# EsquematicoCaneca.net
KiCad netlist of a schematic drawn in Altium Designer
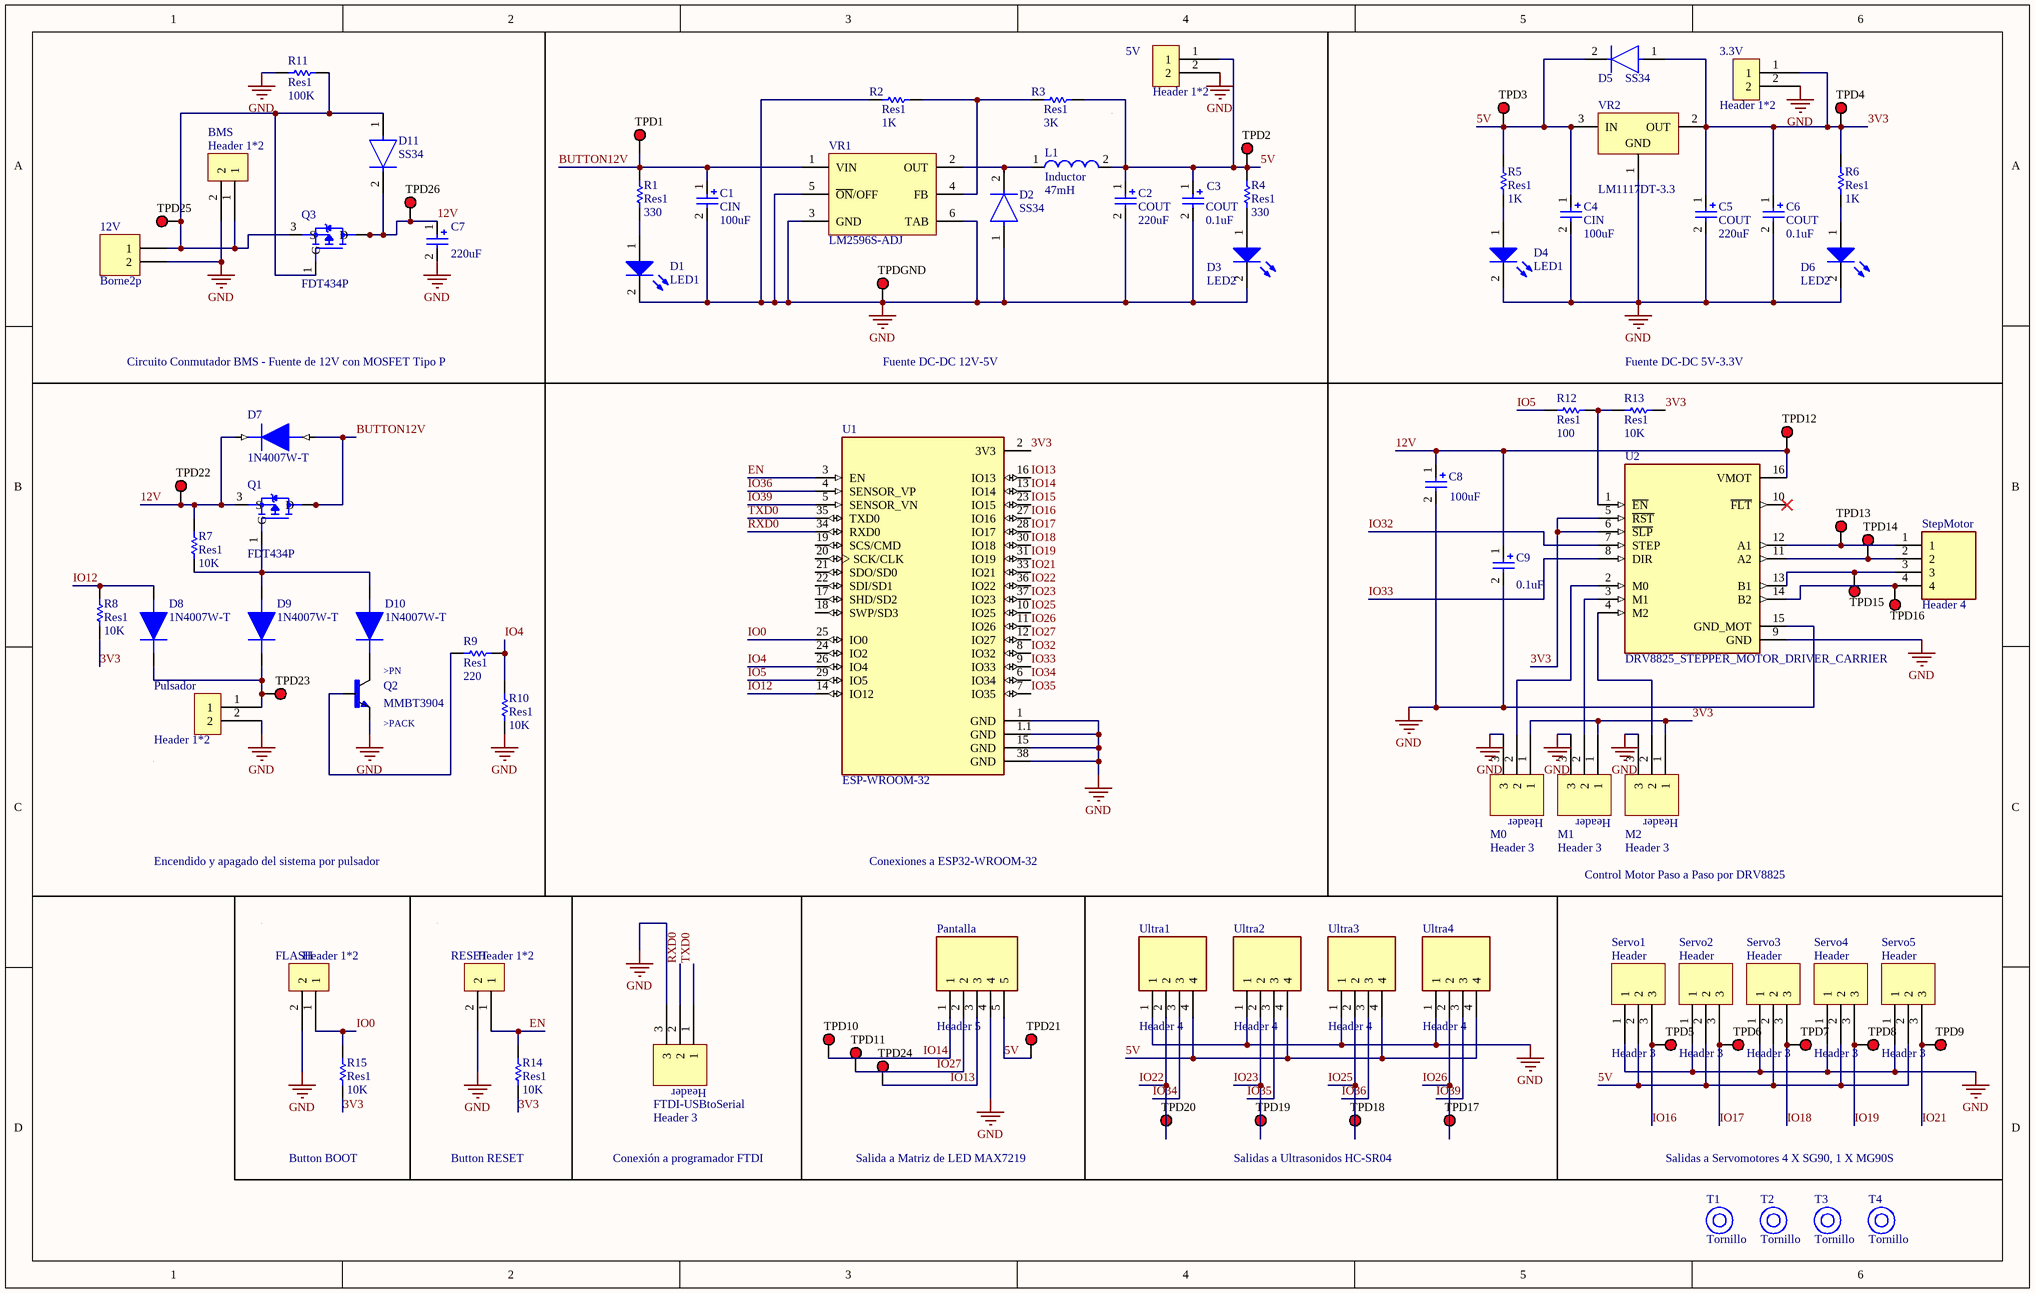
[diagram p0: EsquematicoCaneca.SchDoc]

(export (version "E")
  (design (tool "Eeschema 10.0.6"))
  (components
    (comp (ref "3.3V")
      (value "Header 1*2")
      (footprint "Header 1X2")
      (libsource (lib "ProyectoCaneca") (part "Header 1*2"))
    )
    (comp (ref "5V")
      (value "Header 1*2")
      (footprint "Header 1X2")
      (libsource (lib "ProyectoCaneca") (part "Header 1*2"))
    )
    (comp (ref "12V")
      (value "Borne2p")
      (footprint "Terminal block 1x2 izq")
      (description "Header, 2-Pin")
      (fields (field (name "PUBLISHER") "Altium Limited"))
      (libsource (lib "PCB_Proyecto_Fuente_Voltaje") (part "Header 2"))
    )
    (comp (ref "BMS")
      (value "Header 1*2")
      (footprint "Header 1X2")
      (libsource (lib "") (part "Header 1*2_1"))
    )
    (comp (ref "C1")
      (value "CIN")
      (footprint "CAPACITOR ALUMINUM")
      (description "Polarized Capacitor (Radial)")
      (fields (field (name "ALTIUM_VALUE") "100uF") (field (name "PUBLISHER") "Altium Limited"))
      (libsource (lib "PCB_Proyecto_Fuente_Voltaje") (part "Cap Pol1"))
    )
    (comp (ref "C2")
      (value "COUT")
      (footprint "CAPACITOR ALUMINUM")
      (description "Polarized Capacitor (Radial)")
      (fields (field (name "ALTIUM_VALUE") "220uF") (field (name "PUBLISHER") "Altium Limited"))
      (libsource (lib "PCB_Proyecto_Fuente_Voltaje") (part "Cap Pol1_1"))
    )
    (comp (ref "C3")
      (value "COUT")
      (footprint "CC1206")
      (description "Polarized Capacitor (Radial)")
      (fields (field (name "ALTIUM_VALUE") "0.1uF") (field (name "PUBLISHER") "Altium Limited"))
      (libsource (lib "PCB_Proyecto_Fuente_Voltaje") (part "Cap Pol1_2"))
    )
    (comp (ref "C4")
      (value "CIN")
      (footprint "CAPACITOR ALUMINUM")
      (description "Polarized Capacitor (Radial)")
      (fields (field (name "ALTIUM_VALUE") "100uF") (field (name "PUBLISHER") "Altium Limited"))
      (libsource (lib "PCB_Proyecto_Fuente_Voltaje") (part "Cap Pol1"))
    )
    (comp (ref "C5")
      (value "COUT")
      (footprint "CAPACITOR ALUMINUM")
      (description "Polarized Capacitor (Radial)")
      (fields (field (name "ALTIUM_VALUE") "220uF") (field (name "PUBLISHER") "Altium Limited"))
      (libsource (lib "PCB_Proyecto_Fuente_Voltaje") (part "Cap Pol1_1"))
    )
    (comp (ref "C6")
      (value "COUT")
      (footprint "CC1206")
      (description "Polarized Capacitor (Radial)")
      (fields (field (name "ALTIUM_VALUE") "0.1uF") (field (name "PUBLISHER") "Altium Limited"))
      (libsource (lib "PCB_Proyecto_Fuente_Voltaje") (part "Cap Pol1_2"))
    )
    (comp (ref "C7")
      (value "220uF")
      (footprint "CAPACITOR ALUMINUM")
      (description "Polarized Capacitor (Radial)")
      (fields (field (name "PUBLISHER") "Altium Limited"))
      (libsource (lib "PCB_Proyecto_Fuente_Voltaje") (part "Cap Pol1_1"))
    )
    (comp (ref "C8")
      (value "100uF")
      (footprint "CAPACITOR ALUMINUM")
      (description "Polarized Capacitor (Radial)")
      (fields (field (name "PUBLISHER") "Altium Limited"))
      (libsource (lib "PCB_Proyecto_Fuente_Voltaje") (part "Cap Pol1"))
    )
    (comp (ref "C9")
      (value "0.1uF")
      (footprint "CC1206")
      (description "Polarized Capacitor (Radial)")
      (fields (field (name "PUBLISHER") "Altium Limited"))
      (libsource (lib "PCB_Proyecto_Fuente_Voltaje") (part "Cap Pol1_2"))
    )
    (comp (ref "D1")
      (value "LED1")
      (footprint "LED 0805")
      (description "Typical INFRARED GaAs LED")
      (fields (field (name "PUBLISHER") "Altium Limited"))
      (libsource (lib "PCB_Proyecto_Fuente_Voltaje") (part "LED0_1"))
    )
    (comp (ref "D2")
      (value "SS34")
      (footprint "SS34 DIODE")
      (description "DIODE SCHOTTKY 40V 3A DO214AB")
      (fields (field (name "MANUFACTURER") "Vishay") (field (name "MANUFACTURER PART NUMBER") "SS34-E3/57T"))
      (libsource (lib "biblioteca_esquematica") (part "CMP-02539-000012-1"))
    )
    (comp (ref "D3")
      (value "LED2")
      (footprint "LED 0805")
      (description "Typical INFRARED GaAs LED")
      (fields (field (name "PUBLISHER") "Altium Limited"))
      (libsource (lib "PCB_Proyecto_Fuente_Voltaje") (part "LED0"))
    )
    (comp (ref "D4")
      (value "LED1")
      (footprint "LED 0805")
      (description "Typical INFRARED GaAs LED")
      (fields (field (name "PUBLISHER") "Altium Limited"))
      (libsource (lib "PCB_Proyecto_Fuente_Voltaje") (part "LED0"))
    )
    (comp (ref "D5")
      (value "SS34")
      (footprint "SS34 DIODE")
      (description "DIODE SCHOTTKY 40V 3A DO214AB")
      (fields (field (name "MANUFACTURER") "Vishay") (field (name "MANUFACTURER PART NUMBER") "SS34-E3/57T"))
      (libsource (lib "biblioteca_esquematica") (part "CMP-02539-000012-1"))
    )
    (comp (ref "D6")
      (value "LED2")
      (footprint "LED 0805")
      (description "Typical INFRARED GaAs LED")
      (fields (field (name "PUBLISHER") "Altium Limited"))
      (libsource (lib "PCB_Proyecto_Fuente_Voltaje") (part "LED0"))
    )
    (comp (ref "D7")
      (value "1N4007W-T")
      (footprint "SODFL3818X130N")
      (description "STANDARD SOD123FL T/R 3000")
      (fields (field (name "MF") "EIC") (field (name "MP") "1N4007W"))
      (libsource (lib "ProyectoCaneca") (part "1N4007W-T"))
    )
    (comp (ref "D8")
      (value "1N4007W-T")
      (footprint "SODFL3818X130N")
      (description "STANDARD SOD123FL T/R 3000")
      (fields (field (name "MF") "EIC") (field (name "MP") "1N4007W"))
      (libsource (lib "ProyectoCaneca") (part "1N4007W-T"))
    )
    (comp (ref "D9")
      (value "1N4007W-T")
      (footprint "SODFL3818X130N")
      (description "STANDARD SOD123FL T/R 3000")
      (fields (field (name "MF") "EIC") (field (name "MP") "1N4007W"))
      (libsource (lib "ProyectoCaneca") (part "1N4007W-T"))
    )
    (comp (ref "D10")
      (value "1N4007W-T")
      (footprint "SODFL3818X130N")
      (description "STANDARD SOD123FL T/R 3000")
      (fields (field (name "MF") "EIC") (field (name "MP") "1N4007W"))
      (libsource (lib "ProyectoCaneca") (part "1N4007W-T"))
    )
    (comp (ref "D11")
      (value "SS34")
      (footprint "SS34 DIODE")
      (description "DIODE SCHOTTKY 40V 3A DO214AB")
      (fields (field (name "MANUFACTURER") "Vishay") (field (name "MANUFACTURER PART NUMBER") "SS34-E3/57T"))
      (libsource (lib "biblioteca_esquematica") (part "CMP-02539-000012-1"))
    )
    (comp (ref "FLASH")
      (value "Header 1*2")
      (footprint "Header 1X2")
      (libsource (lib "") (part "Header 1*2_1"))
    )
    (comp (ref "FTDI-USBtoSerial")
      (value "Header 3")
      (footprint "header 1x3")
      (libsource (lib "") (part "Header 3_1"))
    )
    (comp (ref "L1")
      (value "Inductor")
      (footprint "INDUCTOR")
      (fields (field (name "ALTIUM_VALUE") "47mH") (field (name "PUBLISHER") "Altium Limited"))
      (libsource (lib "PCB_Proyecto_Fuente_Voltaje") (part "Inductor"))
    )
    (comp (ref "M0") (value "Header 3") (footprint "header 1x3") (libsource (lib "") (part "Header 3_1")))
    (comp (ref "M1") (value "Header 3") (footprint "header 1x3") (libsource (lib "") (part "Header 3_1")))
    (comp (ref "M2") (value "Header 3") (footprint "header 1x3") (libsource (lib "") (part "Header 3_1")))
    (comp (ref "Pantalla")
      (value "Header 5")
      (footprint "HEADER X 5")
      (description "Board-To-Board Connector, Through Hole, Header, 5, 2.54 mm, Gold Plated Contacts")
      (fields (field (name "MF") "TE Connectivity") (field (name "MP") "826646-5"))
      (libsource (lib "ProyectoCaneca") (part "Header 5"))
    )
    (comp (ref "Pulsador")
      (value "Header 1*2")
      (footprint "Header 1X2")
      (libsource (lib "ProyectoCaneca") (part "Header 1*2"))
    )
    (comp (ref "Q1")
      (value "FDT434P")
      (footprint "SOT230P700X180-4N")
      (description "P-Channel 20 V 6A (Ta) 3W (Ta) Surface Mount SOT-223-4")
      (fields (field (name "MF") "ON"))
      (libsource (lib "ProyectoCaneca") (part "FDT434P"))
    )
    (comp (ref "Q2")
      (value "MMBT3904")
      (footprint "MMBT3904")
      (libsource (lib "ProyectoCaneca") (part "MMBT3904"))
    )
    (comp (ref "Q3")
      (value "FDT434P")
      (footprint "SOT230P700X180-4N")
      (description "P-Channel 20 V 6A (Ta) 3W (Ta) Surface Mount SOT-223-4")
      (fields (field (name "MF") "ON"))
      (libsource (lib "ProyectoCaneca") (part "FDT434P"))
    )
    (comp (ref "R1")
      (value "Res1")
      (footprint "RESISTOR 1206")
      (description "Resistor")
      (fields (field (name "ALTIUM_VALUE") "330") (field (name "PUBLISHER") "Altium Limited"))
      (libsource (lib "PCB_Proyecto_Fuente_Voltaje") (part "Res1_2"))
    )
    (comp (ref "R2")
      (value "Res1")
      (footprint "RESISTOR 1206")
      (description "Resistor")
      (fields (field (name "ALTIUM_VALUE") "1K") (field (name "PUBLISHER") "Altium Limited"))
      (libsource (lib "PCB_Proyecto_Fuente_Voltaje") (part "Res1"))
    )
    (comp (ref "R3")
      (value "Res1")
      (footprint "RESISTOR 1206")
      (description "Resistor")
      (fields (field (name "ALTIUM_VALUE") "3K") (field (name "PUBLISHER") "Altium Limited"))
      (libsource (lib "PCB_Proyecto_Fuente_Voltaje") (part "Res1_1"))
    )
    (comp (ref "R4")
      (value "Res1")
      (footprint "RESISTOR 1206")
      (description "Resistor")
      (fields (field (name "ALTIUM_VALUE") "330") (field (name "PUBLISHER") "Altium Limited"))
      (libsource (lib "PCB_Proyecto_Fuente_Voltaje") (part "Res1_2"))
    )
    (comp (ref "R5")
      (value "Res1")
      (footprint "RESISTOR 1206")
      (description "Resistor")
      (fields (field (name "ALTIUM_VALUE") "1K") (field (name "PUBLISHER") "Altium Limited"))
      (libsource (lib "PCB_Proyecto_Fuente_Voltaje") (part "Res1"))
    )
    (comp (ref "R6")
      (value "Res1")
      (footprint "RESISTOR 1206")
      (description "Resistor")
      (fields (field (name "ALTIUM_VALUE") "1K") (field (name "PUBLISHER") "Altium Limited"))
      (libsource (lib "PCB_Proyecto_Fuente_Voltaje") (part "Res1"))
    )
    (comp (ref "R7")
      (value "Res1")
      (footprint "RESISTOR 1206")
      (description "Resistor")
      (fields (field (name "ALTIUM_VALUE") "10K") (field (name "PUBLISHER") "Altium Limited"))
      (libsource (lib "PCB_Proyecto_Fuente_Voltaje") (part "Res1"))
    )
    (comp (ref "R8")
      (value "Res1")
      (footprint "RESISTOR 1206")
      (description "Resistor")
      (fields (field (name "ALTIUM_VALUE") "10K") (field (name "PUBLISHER") "Altium Limited"))
      (libsource (lib "PCB_Proyecto_Fuente_Voltaje") (part "Res1"))
    )
    (comp (ref "R9")
      (value "Res1")
      (footprint "RESISTOR 1206")
      (description "Resistor")
      (fields (field (name "ALTIUM_VALUE") "220") (field (name "PUBLISHER") "Altium Limited"))
      (libsource (lib "PCB_Proyecto_Fuente_Voltaje") (part "Res1"))
    )
    (comp (ref "R10")
      (value "Res1")
      (footprint "RESISTOR 1206")
      (description "Resistor")
      (fields (field (name "ALTIUM_VALUE") "10K") (field (name "PUBLISHER") "Altium Limited"))
      (libsource (lib "PCB_Proyecto_Fuente_Voltaje") (part "Res1"))
    )
    (comp (ref "R11")
      (value "Res1")
      (footprint "RESISTOR 1206")
      (description "Resistor")
      (fields (field (name "ALTIUM_VALUE") "100K") (field (name "PUBLISHER") "Altium Limited"))
      (libsource (lib "PCB_Proyecto_Fuente_Voltaje") (part "Res1"))
    )
    (comp (ref "R12")
      (value "Res1")
      (footprint "RESISTOR 1206")
      (description "Resistor")
      (fields (field (name "ALTIUM_VALUE") "100") (field (name "PUBLISHER") "Altium Limited"))
      (libsource (lib "PCB_Proyecto_Fuente_Voltaje") (part "Res1"))
    )
    (comp (ref "R13")
      (value "Res1")
      (footprint "RESISTOR 1206")
      (description "Resistor")
      (fields (field (name "ALTIUM_VALUE") "10K") (field (name "PUBLISHER") "Altium Limited"))
      (libsource (lib "PCB_Proyecto_Fuente_Voltaje") (part "Res1"))
    )
    (comp (ref "R14")
      (value "Res1")
      (footprint "RESISTOR 1206")
      (description "Resistor")
      (fields (field (name "ALTIUM_VALUE") "10K") (field (name "PUBLISHER") "Altium Limited"))
      (libsource (lib "PCB_Proyecto_Fuente_Voltaje") (part "Res1"))
    )
    (comp (ref "R15")
      (value "Res1")
      (footprint "RESISTOR 1206")
      (description "Resistor")
      (fields (field (name "ALTIUM_VALUE") "10K") (field (name "PUBLISHER") "Altium Limited"))
      (libsource (lib "PCB_Proyecto_Fuente_Voltaje") (part "Res1"))
    )
    (comp (ref "RESET")
      (value "Header 1*2")
      (footprint "Header 1X2")
      (libsource (lib "") (part "Header 1*2_1"))
    )
    (comp (ref "Servo1")
      (value "Header 3")
      (footprint "header 1x3")
      (libsource (lib "ProyectoCaneca") (part "Header 3"))
    )
    (comp (ref "Servo2")
      (value "Header 3")
      (footprint "header 1x3")
      (libsource (lib "ProyectoCaneca") (part "Header 3"))
    )
    (comp (ref "Servo3")
      (value "Header 3")
      (footprint "header 1x3")
      (libsource (lib "ProyectoCaneca") (part "Header 3"))
    )
    (comp (ref "Servo4")
      (value "Header 3")
      (footprint "header 1x3")
      (libsource (lib "ProyectoCaneca") (part "Header 3"))
    )
    (comp (ref "Servo5")
      (value "Header 3")
      (footprint "header 1x3")
      (libsource (lib "ProyectoCaneca") (part "Header 3"))
    )
    (comp (ref "StepMotor")
      (value "Header 4")
      (footprint "HEADER 1X4")
      (fields (field (name "MP") "640453-4") (field (name "MF") "{'manufacturer': 'TE Connectivity'}"))
      (libsource (lib "") (part "Header 4_1"))
    )
    (comp (ref "T1")
      (value "Tornillo")
      (footprint "TORNILLO")
      (libsource (lib "PCB_Proyecto_Fuente_Voltaje") (part "Tornillo"))
    )
    (comp (ref "T2")
      (value "Tornillo")
      (footprint "TORNILLO")
      (libsource (lib "PCB_Proyecto_Fuente_Voltaje") (part "Tornillo"))
    )
    (comp (ref "T3")
      (value "Tornillo")
      (footprint "TORNILLO")
      (libsource (lib "PCB_Proyecto_Fuente_Voltaje") (part "Tornillo"))
    )
    (comp (ref "T4")
      (value "Tornillo")
      (footprint "TORNILLO")
      (libsource (lib "PCB_Proyecto_Fuente_Voltaje") (part "Tornillo"))
    )
    (comp (ref "TPD1")
      (value "~")
      (footprint "TESTPOINT SMT")
      (description "Test Point, Red, Through Hole, RoHS, Bulk")
      (fields (field (name "MANUFACTURER") "Keystone"))
      (libsource (lib "Schlib2") (part "TestPointRed"))
    )
    (comp (ref "TPD2")
      (value "~")
      (footprint "TESTPOINT SMT")
      (description "Test Point, Red, Through Hole, RoHS, Bulk")
      (fields (field (name "MANUFACTURER") "Keystone"))
      (libsource (lib "Schlib2") (part "TestPointRed"))
    )
    (comp (ref "TPD3")
      (value "~")
      (footprint "TESTPOINT SMT")
      (description "Test Point, Red, Through Hole, RoHS, Bulk")
      (fields (field (name "MANUFACTURER") "Keystone"))
      (libsource (lib "Schlib2") (part "TestPointRed"))
    )
    (comp (ref "TPD4")
      (value "~")
      (footprint "TESTPOINT SMT")
      (description "Test Point, Red, Through Hole, RoHS, Bulk")
      (fields (field (name "MANUFACTURER") "Keystone"))
      (libsource (lib "Schlib2") (part "TestPointRed"))
    )
    (comp (ref "TPD5")
      (value "~")
      (footprint "TESTPOINT SMT")
      (description "Test Point, Red, Through Hole, RoHS, Bulk")
      (fields (field (name "MANUFACTURER") "Keystone"))
      (libsource (lib "Schlib2") (part "TestPointRed"))
    )
    (comp (ref "TPD6")
      (value "~")
      (footprint "TESTPOINT SMT")
      (description "Test Point, Red, Through Hole, RoHS, Bulk")
      (fields (field (name "MANUFACTURER") "Keystone"))
      (libsource (lib "Schlib2") (part "TestPointRed"))
    )
    (comp (ref "TPD7")
      (value "~")
      (footprint "TESTPOINT SMT")
      (description "Test Point, Red, Through Hole, RoHS, Bulk")
      (fields (field (name "MANUFACTURER") "Keystone"))
      (libsource (lib "Schlib2") (part "TestPointRed"))
    )
    (comp (ref "TPD8")
      (value "~")
      (footprint "TESTPOINT SMT")
      (description "Test Point, Red, Through Hole, RoHS, Bulk")
      (fields (field (name "MANUFACTURER") "Keystone"))
      (libsource (lib "Schlib2") (part "TestPointRed"))
    )
    (comp (ref "TPD9")
      (value "~")
      (footprint "TESTPOINT SMT")
      (description "Test Point, Red, Through Hole, RoHS, Bulk")
      (fields (field (name "MANUFACTURER") "Keystone"))
      (libsource (lib "Schlib2") (part "TestPointRed"))
    )
    (comp (ref "TPD10")
      (value "~")
      (footprint "TESTPOINT SMT")
      (description "Test Point, Red, Through Hole, RoHS, Bulk")
      (fields (field (name "MANUFACTURER") "Keystone"))
      (libsource (lib "Schlib2") (part "TestPointRed"))
    )
    (comp (ref "TPD11")
      (value "~")
      (footprint "TESTPOINT SMT")
      (description "Test Point, Red, Through Hole, RoHS, Bulk")
      (fields (field (name "MANUFACTURER") "Keystone"))
      (libsource (lib "Schlib2") (part "TestPointRed"))
    )
    (comp (ref "TPD12")
      (value "~")
      (footprint "TESTPOINT SMT")
      (description "Test Point, Red, Through Hole, RoHS, Bulk")
      (fields (field (name "MANUFACTURER") "Keystone"))
      (libsource (lib "Schlib2") (part "TestPointRed"))
    )
    (comp (ref "TPD13")
      (value "~")
      (footprint "TESTPOINT SMT")
      (description "Test Point, Red, Through Hole, RoHS, Bulk")
      (fields (field (name "MANUFACTURER") "Keystone"))
      (libsource (lib "Schlib2") (part "TestPointRed"))
    )
    (comp (ref "TPD14")
      (value "~")
      (footprint "TESTPOINT SMT")
      (description "Test Point, Red, Through Hole, RoHS, Bulk")
      (fields (field (name "MANUFACTURER") "Keystone"))
      (libsource (lib "Schlib2") (part "TestPointRed"))
    )
    (comp (ref "TPD15")
      (value "~")
      (footprint "TESTPOINT SMT")
      (description "Test Point, Red, Through Hole, RoHS, Bulk")
      (fields (field (name "MANUFACTURER") "Keystone"))
      (libsource (lib "Schlib2") (part "TestPointRed"))
    )
    (comp (ref "TPD16")
      (value "~")
      (footprint "TESTPOINT SMT")
      (description "Test Point, Red, Through Hole, RoHS, Bulk")
      (fields (field (name "MANUFACTURER") "Keystone"))
      (libsource (lib "Schlib2") (part "TestPointRed"))
    )
    (comp (ref "TPD17")
      (value "~")
      (footprint "TESTPOINT SMT")
      (description "Test Point, Red, Through Hole, RoHS, Bulk")
      (fields (field (name "MANUFACTURER") "Keystone"))
      (libsource (lib "Schlib2") (part "TestPointRed"))
    )
    (comp (ref "TPD18")
      (value "~")
      (footprint "TESTPOINT SMT")
      (description "Test Point, Red, Through Hole, RoHS, Bulk")
      (fields (field (name "MANUFACTURER") "Keystone"))
      (libsource (lib "Schlib2") (part "TestPointRed"))
    )
    (comp (ref "TPD19")
      (value "~")
      (footprint "TESTPOINT SMT")
      (description "Test Point, Red, Through Hole, RoHS, Bulk")
      (fields (field (name "MANUFACTURER") "Keystone"))
      (libsource (lib "Schlib2") (part "TestPointRed"))
    )
    (comp (ref "TPD20")
      (value "~")
      (footprint "TESTPOINT SMT")
      (description "Test Point, Red, Through Hole, RoHS, Bulk")
      (fields (field (name "MANUFACTURER") "Keystone"))
      (libsource (lib "Schlib2") (part "TestPointRed"))
    )
    (comp (ref "TPD21")
      (value "~")
      (footprint "TESTPOINT SMT")
      (description "Test Point, Red, Through Hole, RoHS, Bulk")
      (fields (field (name "MANUFACTURER") "Keystone"))
      (libsource (lib "Schlib2") (part "TestPointRed"))
    )
    (comp (ref "TPD22")
      (value "~")
      (footprint "TESTPOINT SMT")
      (description "Test Point, Red, Through Hole, RoHS, Bulk")
      (fields (field (name "MANUFACTURER") "Keystone"))
      (libsource (lib "Schlib2") (part "TestPointRed"))
    )
    (comp (ref "TPD23")
      (value "~")
      (footprint "TESTPOINT SMT")
      (description "Test Point, Red, Through Hole, RoHS, Bulk")
      (fields (field (name "MANUFACTURER") "Keystone"))
      (libsource (lib "Schlib2") (part "TestPointRed"))
    )
    (comp (ref "TPD24")
      (value "~")
      (footprint "TESTPOINT SMT")
      (description "Test Point, Red, Through Hole, RoHS, Bulk")
      (fields (field (name "MANUFACTURER") "Keystone"))
      (libsource (lib "Schlib2") (part "TestPointRed"))
    )
    (comp (ref "TPD25")
      (value "~")
      (footprint "TESTPOINT SMT")
      (description "Test Point, Red, Through Hole, RoHS, Bulk")
      (fields (field (name "MANUFACTURER") "Keystone"))
      (libsource (lib "Schlib2") (part "TestPointRed"))
    )
    (comp (ref "TPD26")
      (value "~")
      (footprint "TESTPOINT SMT")
      (description "Test Point, Red, Through Hole, RoHS, Bulk")
      (fields (field (name "MANUFACTURER") "Keystone"))
      (libsource (lib "Schlib2") (part "TestPointRed"))
    )
    (comp (ref "TPDGND")
      (value "~")
      (footprint "TESTPOINT SMT")
      (description "Test Point, Red, Through Hole, RoHS, Bulk")
      (fields (field (name "MANUFACTURER") "Keystone"))
      (libsource (lib "Schlib2") (part "TestPointRed"))
    )
    (comp (ref "U1")
      (value "ESP-WROOM-32")
      (footprint "MODULE_ESP-WROOM-32")
      (fields (field (name "MF") "Espressif Systems"))
      (libsource (lib "ProyectoCaneca") (part "ESP-WROOM-32"))
    )
    (comp (ref "U2")
      (value "DRV8825_STEPPER_MOTOR_DRIVER_CARRIER")
      (footprint "IC_DRV8825_STEPPER_MOTOR_DRIVER_CARRIER")
      (description "Stepper motor controler; IC: DRV8825; 1.5A; Uin mot: 8.2Ã·45V")
      (libsource (lib "ProyectoCaneca") (part "DRV8825_STEPPER_MOTOR_DRIVER_CARRIER"))
    )
    (comp (ref "Ultra1")
      (value "Header 4")
      (footprint "HEADER 1X4")
      (fields (field (name "MP") "640453-4") (field (name "MF") "{'manufacturer': 'TE Connectivity'}"))
      (libsource (lib "ProyectoCaneca") (part "Header 4"))
    )
    (comp (ref "Ultra2")
      (value "Header 4")
      (footprint "HEADER 1X4")
      (fields (field (name "MP") "640453-4") (field (name "MF") "{'manufacturer': 'TE Connectivity'}"))
      (libsource (lib "ProyectoCaneca") (part "Header 4"))
    )
    (comp (ref "Ultra3")
      (value "Header 4")
      (footprint "HEADER 1X4")
      (fields (field (name "MP") "640453-4") (field (name "MF") "{'manufacturer': 'TE Connectivity'}"))
      (libsource (lib "ProyectoCaneca") (part "Header 4"))
    )
    (comp (ref "Ultra4")
      (value "Header 4")
      (footprint "HEADER 1X4")
      (fields (field (name "MP") "640453-4") (field (name "MF") "{'manufacturer': 'TE Connectivity'}"))
      (libsource (lib "ProyectoCaneca") (part "Header 4"))
    )
    (comp (ref "VR1")
      (value "LM2596S-ADJ")
      (footprint "lm2596S")
      (description "SIMPLE SWITCHER® Power Converter 150 KHz 3A Step-Down Voltage Regulator, 5-pin TO-263")
      (fields
        (field (name "MANUFACTURER") "National Semiconductor")
        (field (name "MANUFACTURER_1") "TI National Semiconductor")
      )
      (libsource (lib "PCB_Proyecto_Fuente_Voltaje") (part "LM2596S-ADJ"))
    )
    (comp (ref "VR2")
      (value "LM1117DT-3.3")
      (footprint "LM1117DT-3.3")
      (description "800mA Low-Dropout Linear Regulator, 3-pin TO-252")
      (fields
        (field (name "MANUFACTURER") "National Semiconductor")
        (field (name "MANUFACTURER_1") "TI National Semiconductor")
      )
      (libsource (lib "PCB_Proyecto_Fuente_Voltaje") (part "LM1117DT-3.3"))
    )
  )
  (nets
    (net (code "1") (name "/3V3") (class "Default")
      (node (ref "3.3V") (pin "1") (pinfunction "1_1") (pintype "passive"))
      (node (ref "C5") (pin "1") (pinfunction "1_1") (pintype "passive"))
      (node (ref "C6") (pin "1") (pinfunction "1_1") (pintype "passive"))
      (node (ref "D5") (pin "1") (pinfunction "A_1") (pintype "passive"))
      (node (ref "M0") (pin "1") (pinfunction "1_1") (pintype "passive"))
      (node (ref "M1") (pin "1") (pinfunction "1_1") (pintype "passive"))
      (node (ref "M2") (pin "1") (pinfunction "1_1") (pintype "passive"))
      (node (ref "R13") (pin "1") (pinfunction "1_1") (pintype "passive"))
      (node (ref "R14") (pin "1") (pinfunction "1_1") (pintype "passive"))
      (node (ref "R15") (pin "1") (pinfunction "1_1") (pintype "passive"))
      (node (ref "R6") (pin "2") (pinfunction "2_2") (pintype "passive"))
      (node (ref "R8") (pin "1") (pinfunction "1_1") (pintype "passive"))
      (node (ref "TPD4") (pin "1") (pinfunction "1_1") (pintype "passive"))
      (node (ref "U1") (pin "2") (pinfunction "3V3_2") (pintype "power_in"))
      (node (ref "U2") (pin "5") (pinfunction "~{RST}_5") (pintype "input"))
      (node (ref "U2") (pin "6") (pinfunction "~{SLP}_6") (pintype "input"))
      (node (ref "VR2") (pin "2") (pinfunction "OUT_2") (pintype "power_in"))
    )
    (net (code "2") (name "/5V") (class "Default")
      (node (ref "5V") (pin "1") (pinfunction "1_1") (pintype "passive"))
      (node (ref "C2") (pin "1") (pinfunction "1_1") (pintype "passive"))
      (node (ref "C3") (pin "1") (pinfunction "1_1") (pintype "passive"))
      (node (ref "C4") (pin "1") (pinfunction "1_1") (pintype "passive"))
      (node (ref "D5") (pin "2") (pinfunction "C_2") (pintype "passive"))
      (node (ref "L1") (pin "2") (pinfunction "2_2") (pintype "passive"))
      (node (ref "Pantalla") (pin "5") (pinfunction "5_5") (pintype "passive"))
      (node (ref "R3") (pin "2") (pinfunction "2_2") (pintype "passive"))
      (node (ref "R4") (pin "2") (pinfunction "2_2") (pintype "passive"))
      (node (ref "R5") (pin "2") (pinfunction "2_2") (pintype "passive"))
      (node (ref "Servo1") (pin "2") (pinfunction "2_2") (pintype "passive"))
      (node (ref "Servo2") (pin "2") (pinfunction "2_2") (pintype "passive"))
      (node (ref "Servo3") (pin "2") (pinfunction "2_2") (pintype "passive"))
      (node (ref "Servo4") (pin "2") (pinfunction "2_2") (pintype "passive"))
      (node (ref "Servo5") (pin "2") (pinfunction "2_2") (pintype "passive"))
      (node (ref "TPD2") (pin "1") (pinfunction "1_1") (pintype "passive"))
      (node (ref "TPD21") (pin "1") (pinfunction "1_1") (pintype "passive"))
      (node (ref "TPD3") (pin "1") (pinfunction "1_1") (pintype "passive"))
      (node (ref "Ultra1") (pin "4") (pinfunction "4_4") (pintype "passive"))
      (node (ref "Ultra2") (pin "4") (pinfunction "4_4") (pintype "passive"))
      (node (ref "Ultra3") (pin "4") (pinfunction "4_4") (pintype "passive"))
      (node (ref "Ultra4") (pin "4") (pinfunction "4_4") (pintype "passive"))
      (node (ref "VR2") (pin "3") (pinfunction "IN_3") (pintype "power_in"))
    )
    (net (code "3") (name "/12V") (class "Default")
      (node (ref "C7") (pin "1") (pinfunction "1_1") (pintype "passive"))
      (node (ref "C8") (pin "1") (pinfunction "1_1") (pintype "passive"))
      (node (ref "C9") (pin "1") (pinfunction "1_1") (pintype "passive"))
      (node (ref "D11") (pin "2") (pinfunction "C_2") (pintype "passive"))
      (node (ref "D7") (pin "1") (pinfunction "K_1") (pintype "bidirectional"))
      (node (ref "Q1") (pin "3") (pinfunction "S_3") (pintype "passive"))
      (node (ref "Q3") (pin "2") (pinfunction "D_2") (pintype "passive"))
      (node (ref "Q3") (pin "4") (pinfunction "D_4") (pintype "passive"))
      (node (ref "R7") (pin "2") (pinfunction "2_2") (pintype "passive"))
      (node (ref "TPD12") (pin "1") (pinfunction "1_1") (pintype "passive"))
      (node (ref "TPD22") (pin "1") (pinfunction "1_1") (pintype "passive"))
      (node (ref "TPD26") (pin "1") (pinfunction "1_1") (pintype "passive"))
      (node (ref "U2") (pin "16") (pinfunction "VMOT_16") (pintype "power_in"))
    )
    (net (code "4") (name "/BUTTON12V") (class "Default")
      (node (ref "C1") (pin "1") (pinfunction "1_1") (pintype "passive"))
      (node (ref "D7") (pin "2") (pinfunction "A_2") (pintype "bidirectional"))
      (node (ref "Q1") (pin "2") (pinfunction "D_2") (pintype "passive"))
      (node (ref "Q1") (pin "4") (pinfunction "D_4") (pintype "passive"))
      (node (ref "R1") (pin "2") (pinfunction "2_2") (pintype "passive"))
      (node (ref "TPD1") (pin "1") (pinfunction "1_1") (pintype "passive"))
      (node (ref "VR1") (pin "1") (pinfunction "VIN_1") (pintype "power_in"))
    )
    (net (code "5") (name "/EN") (class "Default")
      (node (ref "R14") (pin "2") (pinfunction "2_2") (pintype "passive"))
      (node (ref "RESET") (pin "1") (pinfunction "1_1") (pintype "passive"))
      (node (ref "U1") (pin "3") (pinfunction "EN_3") (pintype "input"))
    )
    (net (code "6") (name "/IO0") (class "Default")
      (node (ref "FLASH") (pin "1") (pinfunction "1_1") (pintype "passive"))
      (node (ref "R15") (pin "2") (pinfunction "2_2") (pintype "passive"))
      (node (ref "U1") (pin "25") (pinfunction "IO0_25") (pintype "bidirectional"))
    )
    (net (code "7") (name "/IO4") (class "Default")
      (node (ref "R10") (pin "2") (pinfunction "2_2") (pintype "passive"))
      (node (ref "R9") (pin "2") (pinfunction "2_2") (pintype "passive"))
      (node (ref "U1") (pin "26") (pinfunction "IO4_26") (pintype "bidirectional"))
    )
    (net (code "8") (name "/IO5") (class "Default")
      (node (ref "R12") (pin "1") (pinfunction "1_1") (pintype "passive"))
      (node (ref "U1") (pin "29") (pinfunction "IO5_29") (pintype "bidirectional"))
    )
    (net (code "9") (name "/IO12") (class "Default")
      (node (ref "D8") (pin "2") (pinfunction "A_2") (pintype "bidirectional"))
      (node (ref "R8") (pin "2") (pinfunction "2_2") (pintype "passive"))
      (node (ref "U1") (pin "14") (pinfunction "IO12_14") (pintype "bidirectional"))
    )
    (net (code "10") (name "/IO13") (class "Default")
      (node (ref "Pantalla") (pin "3") (pinfunction "3_3") (pintype "passive"))
      (node (ref "TPD24") (pin "1") (pinfunction "1_1") (pintype "passive"))
      (node (ref "U1") (pin "16") (pinfunction "IO13_16") (pintype "bidirectional"))
    )
    (net (code "11") (name "/IO14") (class "Default")
      (node (ref "Pantalla") (pin "1") (pinfunction "1_1") (pintype "passive"))
      (node (ref "TPD10") (pin "1") (pinfunction "1_1") (pintype "passive"))
      (node (ref "U1") (pin "13") (pinfunction "IO14_13") (pintype "bidirectional"))
    )
    (net (code "12") (name "/IO15") (class "Default")
      (node (ref "U1") (pin "23") (pinfunction "IO15_23") (pintype "bidirectional"))
    )
    (net (code "13") (name "/IO16") (class "Default")
      (node (ref "Servo1") (pin "3") (pinfunction "3_3") (pintype "passive"))
      (node (ref "TPD5") (pin "1") (pinfunction "1_1") (pintype "passive"))
      (node (ref "U1") (pin "27") (pinfunction "IO16_27") (pintype "bidirectional"))
    )
    (net (code "14") (name "/IO17") (class "Default")
      (node (ref "Servo2") (pin "3") (pinfunction "3_3") (pintype "passive"))
      (node (ref "TPD6") (pin "1") (pinfunction "1_1") (pintype "passive"))
      (node (ref "U1") (pin "28") (pinfunction "IO17_28") (pintype "bidirectional"))
    )
    (net (code "15") (name "/IO18") (class "Default")
      (node (ref "Servo3") (pin "3") (pinfunction "3_3") (pintype "passive"))
      (node (ref "TPD7") (pin "1") (pinfunction "1_1") (pintype "passive"))
      (node (ref "U1") (pin "30") (pinfunction "IO18_30") (pintype "bidirectional"))
    )
    (net (code "16") (name "/IO19") (class "Default")
      (node (ref "Servo4") (pin "3") (pinfunction "3_3") (pintype "passive"))
      (node (ref "TPD8") (pin "1") (pinfunction "1_1") (pintype "passive"))
      (node (ref "U1") (pin "31") (pinfunction "IO19_31") (pintype "bidirectional"))
    )
    (net (code "17") (name "/IO21") (class "Default")
      (node (ref "Servo5") (pin "3") (pinfunction "3_3") (pintype "passive"))
      (node (ref "TPD9") (pin "1") (pinfunction "1_1") (pintype "passive"))
      (node (ref "U1") (pin "33") (pinfunction "IO21_33") (pintype "bidirectional"))
    )
    (net (code "18") (name "/IO22") (class "Default")
      (node (ref "TPD20") (pin "1") (pinfunction "1_1") (pintype "passive"))
      (node (ref "U1") (pin "36") (pinfunction "IO22_36") (pintype "bidirectional"))
      (node (ref "Ultra1") (pin "2") (pinfunction "2_2") (pintype "passive"))
    )
    (net (code "19") (name "/IO23") (class "Default")
      (node (ref "TPD19") (pin "1") (pinfunction "1_1") (pintype "passive"))
      (node (ref "U1") (pin "37") (pinfunction "IO23_37") (pintype "bidirectional"))
      (node (ref "Ultra2") (pin "2") (pinfunction "2_2") (pintype "passive"))
    )
    (net (code "20") (name "/IO25") (class "Default")
      (node (ref "TPD18") (pin "1") (pinfunction "1_1") (pintype "passive"))
      (node (ref "U1") (pin "10") (pinfunction "IO25_10") (pintype "bidirectional"))
      (node (ref "Ultra3") (pin "2") (pinfunction "2_2") (pintype "passive"))
    )
    (net (code "21") (name "/IO26") (class "Default")
      (node (ref "TPD17") (pin "1") (pinfunction "1_1") (pintype "passive"))
      (node (ref "U1") (pin "11") (pinfunction "IO26_11") (pintype "bidirectional"))
      (node (ref "Ultra4") (pin "2") (pinfunction "2_2") (pintype "passive"))
    )
    (net (code "22") (name "/IO27") (class "Default")
      (node (ref "Pantalla") (pin "2") (pinfunction "2_2") (pintype "passive"))
      (node (ref "TPD11") (pin "1") (pinfunction "1_1") (pintype "passive"))
      (node (ref "U1") (pin "12") (pinfunction "IO27_12") (pintype "bidirectional"))
    )
    (net (code "23") (name "/IO32") (class "Default")
      (node (ref "U1") (pin "8") (pinfunction "IO32_8") (pintype "bidirectional"))
      (node (ref "U2") (pin "7") (pinfunction "STEP_7") (pintype "input"))
    )
    (net (code "24") (name "/IO33") (class "Default")
      (node (ref "U1") (pin "9") (pinfunction "IO33_9") (pintype "bidirectional"))
      (node (ref "U2") (pin "8") (pinfunction "DIR_8") (pintype "input"))
    )
    (net (code "25") (name "/IO34") (class "Default")
      (node (ref "U1") (pin "6") (pinfunction "IO34_6") (pintype "bidirectional"))
      (node (ref "Ultra1") (pin "3") (pinfunction "3_3") (pintype "passive"))
    )
    (net (code "26") (name "/IO35") (class "Default")
      (node (ref "U1") (pin "7") (pinfunction "IO35_7") (pintype "bidirectional"))
      (node (ref "Ultra2") (pin "3") (pinfunction "3_3") (pintype "passive"))
    )
    (net (code "27") (name "/IO36") (class "Default")
      (node (ref "U1") (pin "4") (pinfunction "SENSOR_VP_4") (pintype "input"))
      (node (ref "Ultra3") (pin "3") (pinfunction "3_3") (pintype "passive"))
    )
    (net (code "28") (name "/IO39") (class "Default")
      (node (ref "U1") (pin "5") (pinfunction "SENSOR_VN_5") (pintype "input"))
      (node (ref "Ultra4") (pin "3") (pinfunction "3_3") (pintype "passive"))
    )
    (net (code "29") (name "/RXD0") (class "Default")
      (node (ref "FTDI-USBtoSerial") (pin "2") (pinfunction "2_2") (pintype "passive"))
      (node (ref "U1") (pin "34") (pinfunction "RXD0_34") (pintype "bidirectional"))
    )
    (net (code "30") (name "/TXD0") (class "Default")
      (node (ref "FTDI-USBtoSerial") (pin "1") (pinfunction "1_1") (pintype "passive"))
      (node (ref "U1") (pin "35") (pinfunction "TXD0_35") (pintype "bidirectional"))
    )
    (net (code "31") (name "GND") (class "Default")
      (node (ref "12V") (pin "2") (pinfunction "2_2") (pintype "passive"))
      (node (ref "3.3V") (pin "2") (pinfunction "2_2") (pintype "passive"))
      (node (ref "5V") (pin "2") (pinfunction "2_2") (pintype "passive"))
      (node (ref "BMS") (pin "2") (pinfunction "2_2") (pintype "passive"))
      (node (ref "C1") (pin "2") (pinfunction "2_2") (pintype "passive"))
      (node (ref "C2") (pin "2") (pinfunction "2_2") (pintype "passive"))
      (node (ref "C3") (pin "2") (pinfunction "2_2") (pintype "passive"))
      (node (ref "C4") (pin "2") (pinfunction "2_2") (pintype "passive"))
      (node (ref "C5") (pin "2") (pinfunction "2_2") (pintype "passive"))
      (node (ref "C6") (pin "2") (pinfunction "2_2") (pintype "passive"))
      (node (ref "C7") (pin "2") (pinfunction "2_2") (pintype "passive"))
      (node (ref "C8") (pin "2") (pinfunction "2_2") (pintype "passive"))
      (node (ref "C9") (pin "2") (pinfunction "2_2") (pintype "passive"))
      (node (ref "D1") (pin "2") (pinfunction "K_2") (pintype "passive"))
      (node (ref "D2") (pin "1") (pinfunction "A_1") (pintype "passive"))
      (node (ref "D3") (pin "2") (pinfunction "K_2") (pintype "passive"))
      (node (ref "D4") (pin "2") (pinfunction "K_2") (pintype "passive"))
      (node (ref "D6") (pin "2") (pinfunction "K_2") (pintype "passive"))
      (node (ref "FLASH") (pin "2") (pinfunction "2_2") (pintype "passive"))
      (node (ref "FTDI-USBtoSerial") (pin "3") (pinfunction "3_3") (pintype "passive"))
      (node (ref "M0") (pin "3") (pinfunction "3_3") (pintype "passive"))
      (node (ref "M1") (pin "3") (pinfunction "3_3") (pintype "passive"))
      (node (ref "M2") (pin "3") (pinfunction "3_3") (pintype "passive"))
      (node (ref "Pantalla") (pin "4") (pinfunction "4_4") (pintype "passive"))
      (node (ref "Pulsador") (pin "2") (pinfunction "2_2") (pintype "passive"))
      (node (ref "Q2") (pin "2") (pinfunction "E_2") (pintype "passive"))
      (node (ref "R10") (pin "1") (pinfunction "1_1") (pintype "passive"))
      (node (ref "R11") (pin "2") (pinfunction "2_2") (pintype "passive"))
      (node (ref "R2") (pin "1") (pinfunction "1_1") (pintype "passive"))
      (node (ref "RESET") (pin "2") (pinfunction "2_2") (pintype "passive"))
      (node (ref "Servo1") (pin "1") (pinfunction "1_1") (pintype "passive"))
      (node (ref "Servo2") (pin "1") (pinfunction "1_1") (pintype "passive"))
      (node (ref "Servo3") (pin "1") (pinfunction "1_1") (pintype "passive"))
      (node (ref "Servo4") (pin "1") (pinfunction "1_1") (pintype "passive"))
      (node (ref "Servo5") (pin "1") (pinfunction "1_1") (pintype "passive"))
      (node (ref "TPDGND") (pin "1") (pinfunction "1_1") (pintype "passive"))
      (node (ref "U1") (pin "1") (pinfunction "GND_1") (pintype "power_in"))
      (node (ref "U1") (pin "1.1") (pinfunction "GND_1.1") (pintype "power_in"))
      (node (ref "U1") (pin "15") (pinfunction "GND_15") (pintype "power_in"))
      (node (ref "U1") (pin "38") (pinfunction "GND_38") (pintype "power_in"))
      (node (ref "U2") (pin "15") (pinfunction "GND_MOT_15") (pintype "power_in"))
      (node (ref "U2") (pin "9") (pinfunction "GND_9") (pintype "power_in"))
      (node (ref "Ultra1") (pin "1") (pinfunction "1_1") (pintype "passive"))
      (node (ref "Ultra2") (pin "1") (pinfunction "1_1") (pintype "passive"))
      (node (ref "Ultra3") (pin "1") (pinfunction "1_1") (pintype "passive"))
      (node (ref "Ultra4") (pin "1") (pinfunction "1_1") (pintype "passive"))
      (node (ref "VR1") (pin "3") (pinfunction "GND_3") (pintype "power_in"))
      (node (ref "VR1") (pin "5") (pinfunction "~{ON}/OFF_5") (pintype "passive"))
      (node (ref "VR1") (pin "6") (pinfunction "TAB_6") (pintype "power_in"))
      (node (ref "VR2") (pin "1") (pinfunction "GND_1") (pintype "power_in"))
    )
    (net (code "32") (name "Net-(D1-A)") (class "Default")
      (node (ref "D1") (pin "1") (pinfunction "A_1") (pintype "passive"))
      (node (ref "R1") (pin "1") (pinfunction "1_1") (pintype "passive"))
    )
    (net (code "33") (name "Net-(D2-C)") (class "Default")
      (node (ref "D2") (pin "2") (pinfunction "C_2") (pintype "passive"))
      (node (ref "L1") (pin "1") (pinfunction "1_1") (pintype "passive"))
      (node (ref "VR1") (pin "2") (pinfunction "OUT_2") (pintype "power_in"))
    )
    (net (code "34") (name "Net-(D3-A)") (class "Default")
      (node (ref "D3") (pin "1") (pinfunction "A_1") (pintype "passive"))
      (node (ref "R4") (pin "1") (pinfunction "1_1") (pintype "passive"))
    )
    (net (code "35") (name "Net-(D4-A)") (class "Default")
      (node (ref "D4") (pin "1") (pinfunction "A_1") (pintype "passive"))
      (node (ref "R5") (pin "1") (pinfunction "1_1") (pintype "passive"))
    )
    (net (code "36") (name "Net-(D6-A)") (class "Default")
      (node (ref "D6") (pin "1") (pinfunction "A_1") (pintype "passive"))
      (node (ref "R6") (pin "1") (pinfunction "1_1") (pintype "passive"))
    )
    (net (code "37") (name "Net-(D8-K)") (class "Default")
      (node (ref "D8") (pin "1") (pinfunction "K_1") (pintype "bidirectional"))
      (node (ref "D9") (pin "1") (pinfunction "K_1") (pintype "bidirectional"))
      (node (ref "Pulsador") (pin "1") (pinfunction "1_1") (pintype "passive"))
      (node (ref "TPD23") (pin "1") (pinfunction "1_1") (pintype "passive"))
    )
    (net (code "38") (name "Net-(D10-A)") (class "Default")
      (node (ref "D10") (pin "2") (pinfunction "A_2") (pintype "bidirectional"))
      (node (ref "D9") (pin "2") (pinfunction "A_2") (pintype "bidirectional"))
      (node (ref "Q1") (pin "1") (pinfunction "G_1") (pintype "passive"))
      (node (ref "R7") (pin "1") (pinfunction "1_1") (pintype "passive"))
    )
    (net (code "39") (name "Net-(D10-K)") (class "Default")
      (node (ref "D10") (pin "1") (pinfunction "K_1") (pintype "bidirectional"))
      (node (ref "Q2") (pin "3") (pinfunction "C_3") (pintype "passive"))
    )
    (net (code "40") (name "Net-(D11-A)") (class "Default")
      (node (ref "12V") (pin "1") (pinfunction "1_1") (pintype "passive"))
      (node (ref "BMS") (pin "1") (pinfunction "1_1") (pintype "passive"))
      (node (ref "D11") (pin "1") (pinfunction "A_1") (pintype "passive"))
      (node (ref "Q3") (pin "1") (pinfunction "G_1") (pintype "passive"))
      (node (ref "Q3") (pin "3") (pinfunction "S_3") (pintype "passive"))
      (node (ref "R11") (pin "1") (pinfunction "1_1") (pintype "passive"))
      (node (ref "TPD25") (pin "1") (pinfunction "1_1") (pintype "passive"))
    )
    (net (code "41") (name "Net-(Q2-B)") (class "Default")
      (node (ref "Q2") (pin "1") (pinfunction "B_1") (pintype "passive"))
      (node (ref "R9") (pin "1") (pinfunction "1_1") (pintype "passive"))
    )
    (net (code "42") (name "Net-(U2-A1)") (class "Default")
      (node (ref "StepMotor") (pin "1") (pinfunction "1_1") (pintype "passive"))
      (node (ref "TPD13") (pin "1") (pinfunction "1_1") (pintype "passive"))
      (node (ref "U2") (pin "12") (pinfunction "A1_12") (pintype "output"))
    )
    (net (code "43") (name "Net-(U2-A2)") (class "Default")
      (node (ref "StepMotor") (pin "2") (pinfunction "2_2") (pintype "passive"))
      (node (ref "TPD14") (pin "1") (pinfunction "1_1") (pintype "passive"))
      (node (ref "U2") (pin "11") (pinfunction "A2_11") (pintype "output"))
    )
    (net (code "44") (name "Net-(U2-B1)") (class "Default")
      (node (ref "StepMotor") (pin "3") (pinfunction "3_3") (pintype "passive"))
      (node (ref "TPD15") (pin "1") (pinfunction "1_1") (pintype "passive"))
      (node (ref "U2") (pin "13") (pinfunction "B1_13") (pintype "output"))
    )
    (net (code "45") (name "Net-(U2-B2)") (class "Default")
      (node (ref "StepMotor") (pin "4") (pinfunction "4_4") (pintype "passive"))
      (node (ref "TPD16") (pin "1") (pinfunction "1_1") (pintype "passive"))
      (node (ref "U2") (pin "14") (pinfunction "B2_14") (pintype "output"))
    )
    (net (code "46") (name "Net-(U2-M0)") (class "Default")
      (node (ref "M0") (pin "2") (pinfunction "2_2") (pintype "passive"))
      (node (ref "U2") (pin "2") (pinfunction "M0_2") (pintype "input"))
    )
    (net (code "47") (name "Net-(U2-M1)") (class "Default")
      (node (ref "M1") (pin "2") (pinfunction "2_2") (pintype "passive"))
      (node (ref "U2") (pin "3") (pinfunction "M1_3") (pintype "input"))
    )
    (net (code "48") (name "Net-(U2-M2)") (class "Default")
      (node (ref "M2") (pin "2") (pinfunction "2_2") (pintype "passive"))
      (node (ref "U2") (pin "4") (pinfunction "M2_4") (pintype "input"))
    )
    (net (code "49") (name "Net-(U2-~{EN})") (class "Default")
      (node (ref "R12") (pin "2") (pinfunction "2_2") (pintype "passive"))
      (node (ref "R13") (pin "2") (pinfunction "2_2") (pintype "passive"))
      (node (ref "U2") (pin "1") (pinfunction "~{EN}_1") (pintype "input"))
    )
    (net (code "50") (name "Net-(VR1-FB)") (class "Default")
      (node (ref "R2") (pin "2") (pinfunction "2_2") (pintype "passive"))
      (node (ref "R3") (pin "1") (pinfunction "1_1") (pintype "passive"))
      (node (ref "VR1") (pin "4") (pinfunction "FB_4") (pintype "passive"))
    )
    (net (code "51") (name "unconnected-(U1-IO2-Pad24)") (class "Default")
      (node (ref "U1") (pin "24") (pinfunction "IO2_24") (pintype "bidirectional"))
    )
    (net (code "52") (name "unconnected-(U1-SCK{slash}CLK-Pad20)") (class "Default")
      (node (ref "U1") (pin "20") (pinfunction "SCK/CLK_20") (pintype "bidirectional"))
    )
    (net (code "53") (name "unconnected-(U1-SCS{slash}CMD-Pad19)") (class "Default")
      (node (ref "U1") (pin "19") (pinfunction "SCS/CMD_19") (pintype "bidirectional"))
    )
    (net (code "54") (name "unconnected-(U1-SDI{slash}SD1-Pad22)") (class "Default")
      (node (ref "U1") (pin "22") (pinfunction "SDI/SD1_22") (pintype "bidirectional"))
    )
    (net (code "55") (name "unconnected-(U1-SDO{slash}SD0-Pad21)") (class "Default")
      (node (ref "U1") (pin "21") (pinfunction "SDO/SD0_21") (pintype "bidirectional"))
    )
    (net (code "56") (name "unconnected-(U1-SHD{slash}SD2-Pad17)") (class "Default")
      (node (ref "U1") (pin "17") (pinfunction "SHD/SD2_17") (pintype "bidirectional"))
    )
    (net (code "57") (name "unconnected-(U1-SWP{slash}SD3-Pad18)") (class "Default")
      (node (ref "U1") (pin "18") (pinfunction "SWP/SD3_18") (pintype "bidirectional"))
    )
    (net (code "58") (name "unconnected-(U2-~{FLT}-Pad10)") (class "Default")
      (node (ref "U2") (pin "10") (pinfunction "~{FLT}_10") (pintype "output+no_connect"))
    )
  )
)
